# Adafruit_Crickit_for_Circuit_Playground.net
KiCad netlist of a schematic drawn in EAGLE
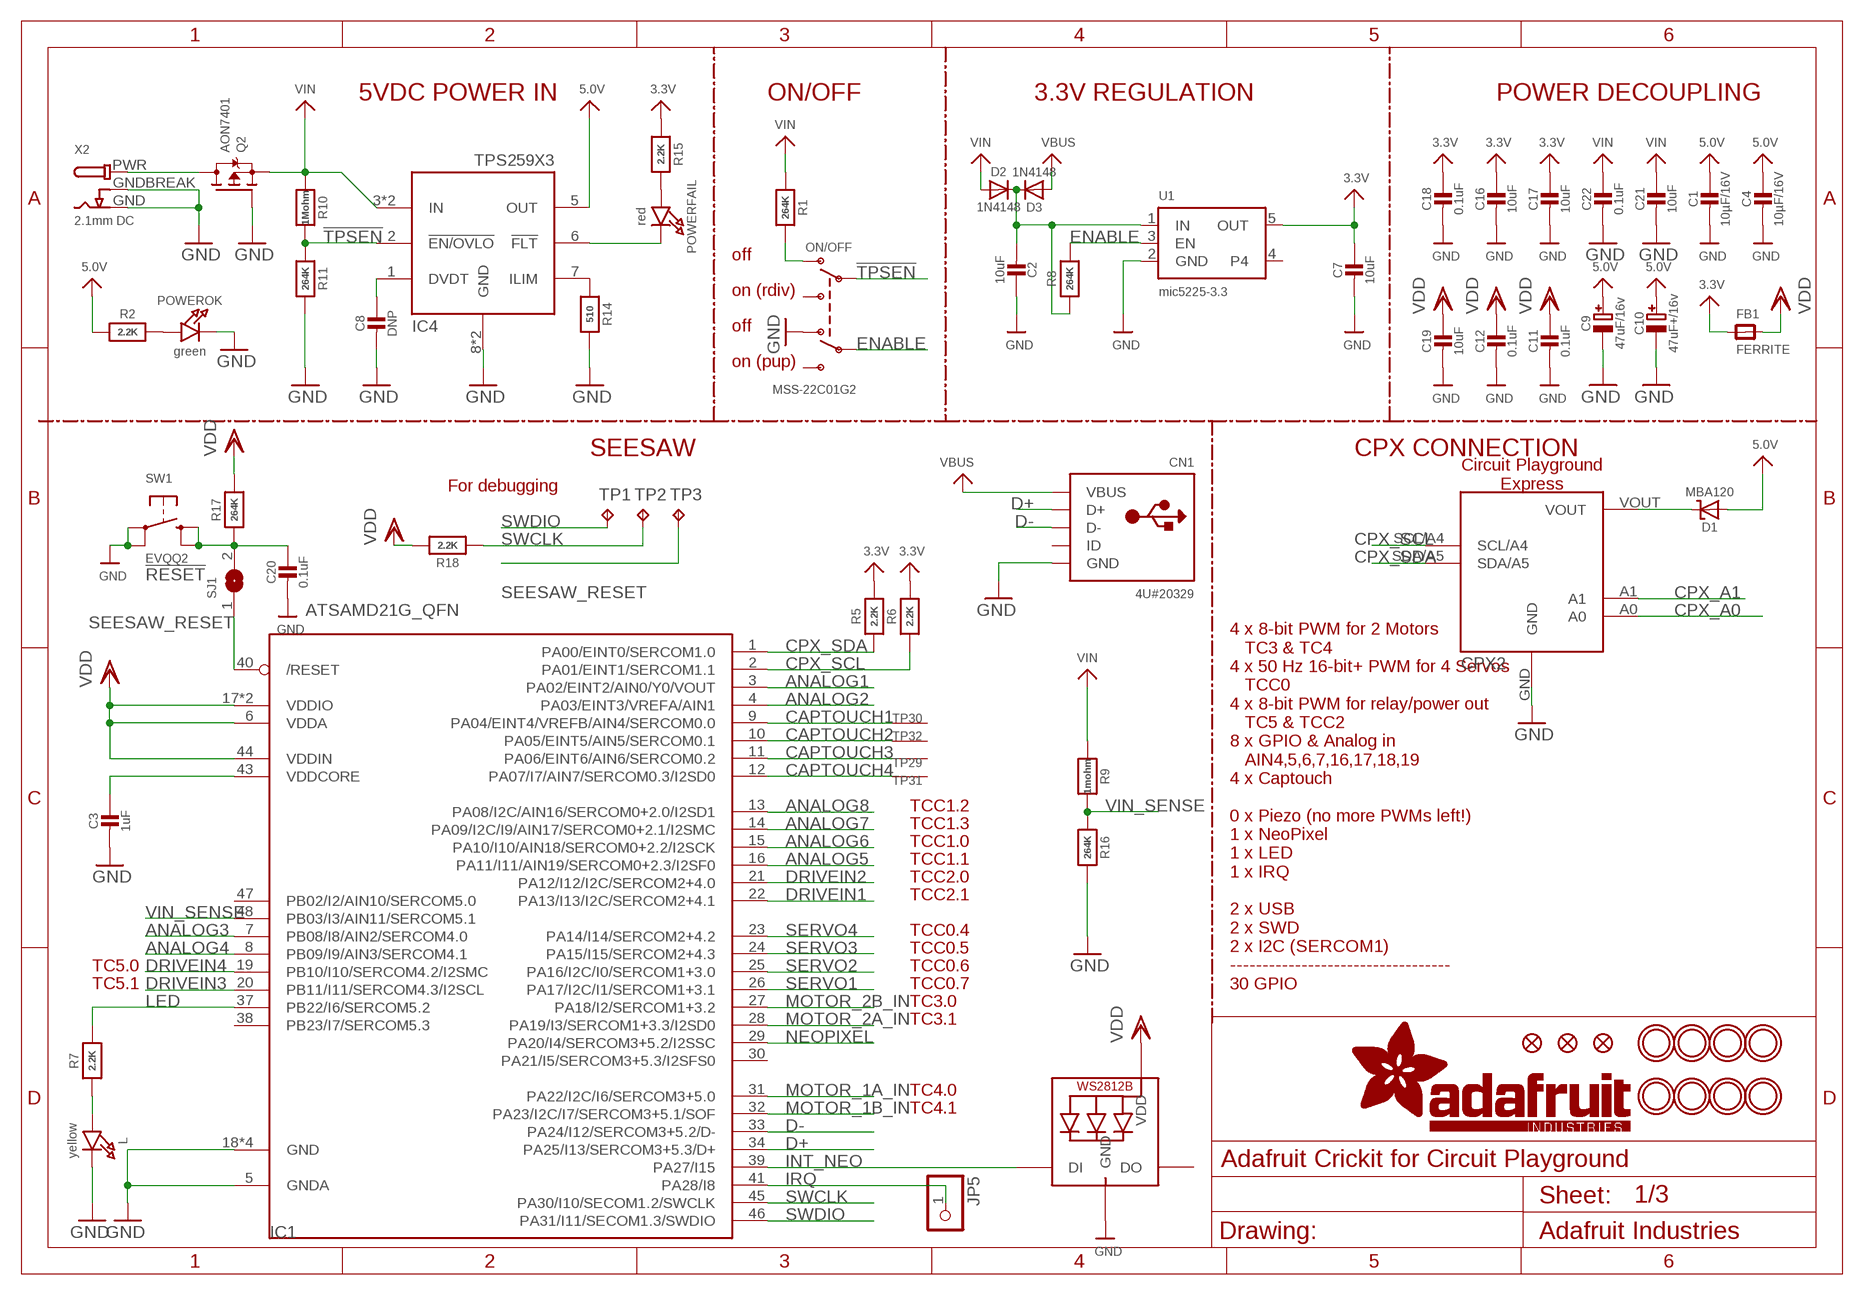
[diagram p0: schematic, sheet 1]
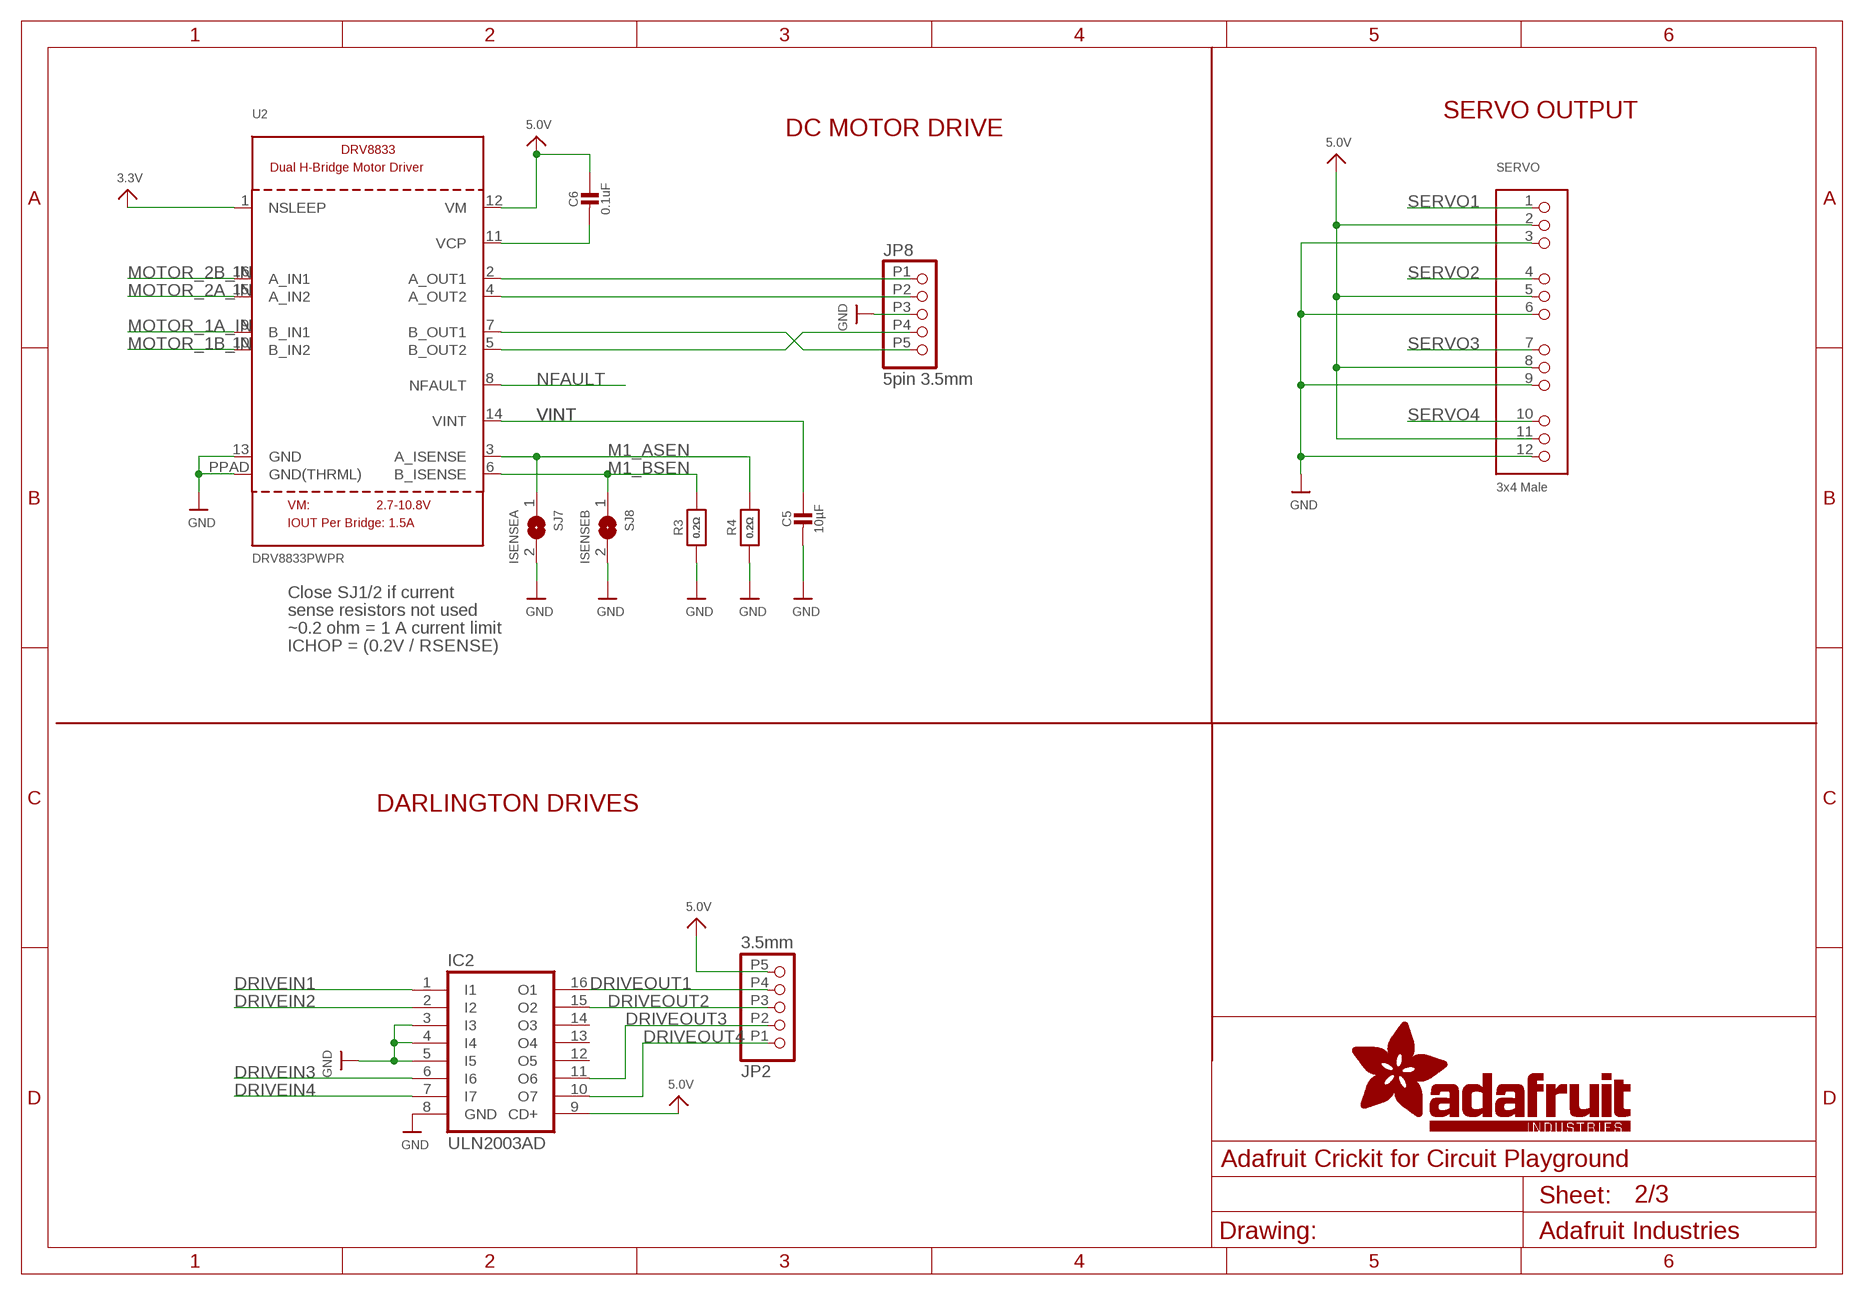
[diagram p1: schematic, sheet 2]
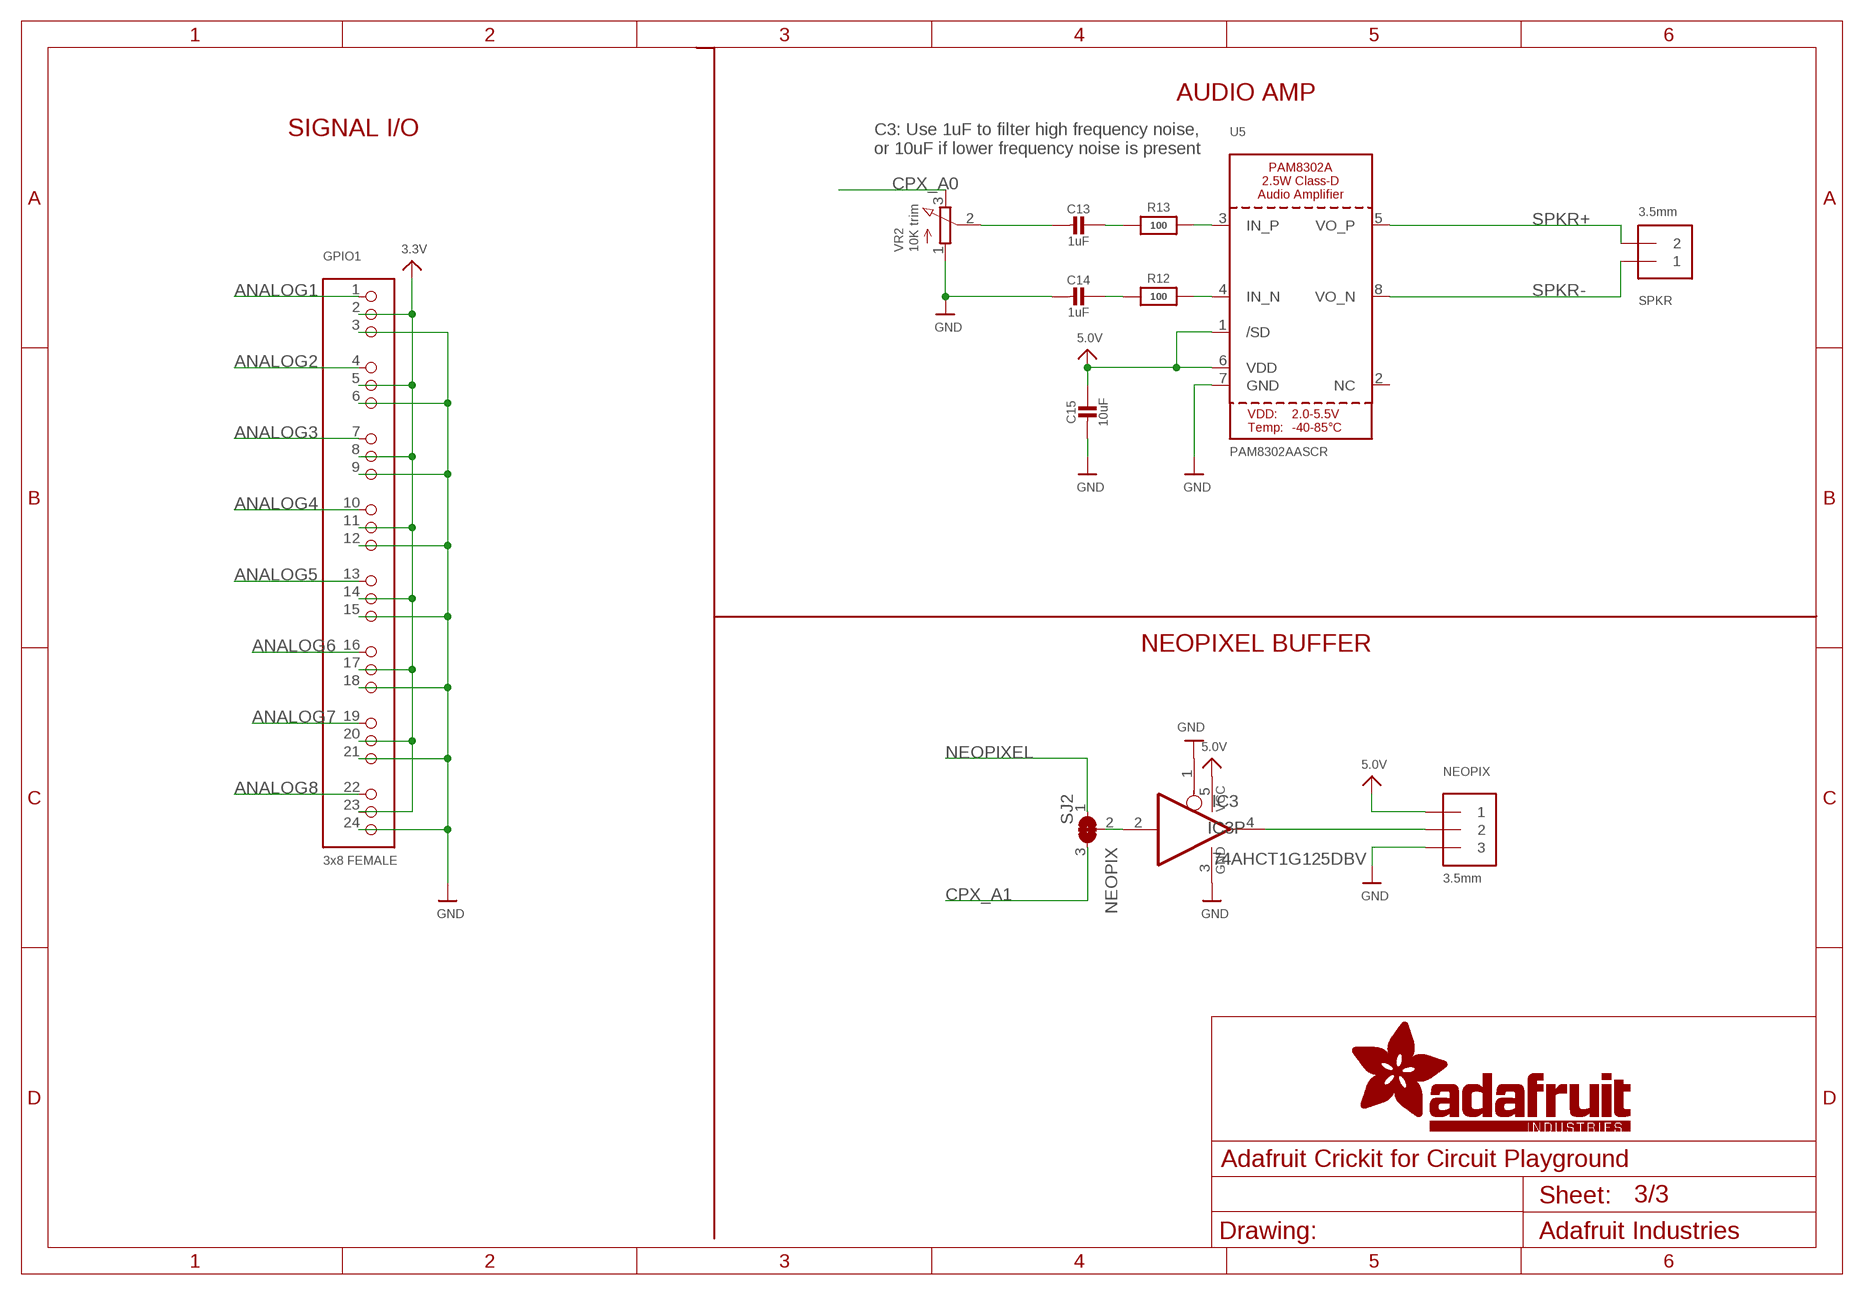
[diagram p2: schematic, sheet 3]

(export (version "E")
  (design (tool "Eeschema 10.0.6"))
  (components
    (comp (ref "C1")
      (value "10µF/16V")
      (footprint "eagle-import:0805-NO")
      (libsource (lib "eagle-import") (part "CAP_CERAMIC0805-NOOUTLINE"))
    )
    (comp (ref "C2")
      (value "10uF")
      (footprint "eagle-import:0805-NO")
      (libsource (lib "eagle-import") (part "CAP_CERAMIC0805-NOOUTLINE"))
    )
    (comp (ref "C3")
      (value "1uF")
      (footprint "eagle-import:0805_10MGAP")
      (libsource (lib "eagle-import") (part "CAP_CERAMIC0805_10MGAP"))
    )
    (comp (ref "C4")
      (value "10µF/16V")
      (footprint "eagle-import:0805-NO")
      (libsource (lib "eagle-import") (part "CAP_CERAMIC0805-NOOUTLINE"))
    )
    (comp (ref "C7")
      (value "10uF")
      (footprint "eagle-import:0805-NO")
      (libsource (lib "eagle-import") (part "CAP_CERAMIC0805-NOOUTLINE"))
    )
    (comp (ref "C8")
      (value "DNP")
      (footprint "eagle-import:0603-NO")
      (libsource (lib "eagle-import") (part "CAP_CERAMIC0603_NO"))
    )
    (comp (ref "C9")
      (value "47uF/16v")
      (footprint "eagle-import:PANASONIC_C")
      (libsource (lib "eagle-import") (part "CAP_ELECTROLYTICPANASONIC_C"))
    )
    (comp (ref "C10")
      (value "47uF+/16v")
      (footprint "eagle-import:PANASONIC_C")
      (libsource (lib "eagle-import") (part "CAP_ELECTROLYTICPANASONIC_C"))
    )
    (comp (ref "C11")
      (value "0.1uF")
      (footprint "eagle-import:0805-NO")
      (libsource (lib "eagle-import") (part "CAP_CERAMIC0805-NOOUTLINE"))
    )
    (comp (ref "C12")
      (value "0.1uF")
      (footprint "eagle-import:0603-NO")
      (libsource (lib "eagle-import") (part "CAP_CERAMIC0603_NO"))
    )
    (comp (ref "C16")
      (value "10uF")
      (footprint "eagle-import:0805-NO")
      (libsource (lib "eagle-import") (part "CAP_CERAMIC0805-NOOUTLINE"))
    )
    (comp (ref "C17")
      (value "10uF")
      (footprint "eagle-import:0805-NO")
      (libsource (lib "eagle-import") (part "CAP_CERAMIC0805-NOOUTLINE"))
    )
    (comp (ref "C18")
      (value "0.1uF")
      (footprint "eagle-import:0805-NO")
      (libsource (lib "eagle-import") (part "CAP_CERAMIC0805-NOOUTLINE"))
    )
    (comp (ref "C19")
      (value "10uF")
      (footprint "eagle-import:0805-NO")
      (libsource (lib "eagle-import") (part "CAP_CERAMIC0805-NOOUTLINE"))
    )
    (comp (ref "C20")
      (value "0.1uF")
      (footprint "eagle-import:0805-NO")
      (libsource (lib "eagle-import") (part "CAP_CERAMIC0805-NOOUTLINE"))
    )
    (comp (ref "C21")
      (value "10uF")
      (footprint "eagle-import:0805-NO")
      (libsource (lib "eagle-import") (part "CAP_CERAMIC0805-NOOUTLINE"))
    )
    (comp (ref "C22")
      (value "0.1uF")
      (footprint "eagle-import:0805-NO")
      (libsource (lib "eagle-import") (part "CAP_CERAMIC0805-NOOUTLINE"))
    )
    (comp (ref "CN1")
      (value "4U#20329")
      (footprint "eagle-import:4UCONN_20329_V2")
      (libsource (lib "eagle-import") (part "USB_MICRO_20329_V2"))
    )
    (comp (ref "CPX2")
      (value "CPX_CRICKIT")
      (footprint "eagle-import:CPX_CRICKIT")
      (libsource (lib "eagle-import") (part "CPX_CRICKIT"))
    )
    (comp (ref "D1")
      (value "MBA120")
      (footprint "eagle-import:SOD-123")
      (libsource (lib "eagle-import") (part "DIODE-SCHOTTKYSOD-123"))
    )
    (comp (ref "D2")
      (value "1N4148")
      (footprint "eagle-import:SOD-323")
      (libsource (lib "eagle-import") (part "DIODESOD-323"))
    )
    (comp (ref "D3")
      (value "1N4148")
      (footprint "eagle-import:SOD-323")
      (libsource (lib "eagle-import") (part "DIODESOD-323"))
    )
    (comp (ref "FB1")
      (value "FERRITE")
      (footprint "eagle-import:0805-NO")
      (libsource (lib "eagle-import") (part "FERRITE-0805NO"))
    )
    (comp (ref "FID1")
      (value "FIDUCIAL_1MM")
      (footprint "eagle-import:FIDUCIAL_1MM")
      (libsource (lib "eagle-import") (part "FIDUCIAL_1MM"))
    )
    (comp (ref "FID2")
      (value "FIDUCIAL_1MM")
      (footprint "eagle-import:FIDUCIAL_1MM")
      (libsource (lib "eagle-import") (part "FIDUCIAL_1MM"))
    )
    (comp (ref "FID3")
      (value "FIDUCIAL_1MM")
      (footprint "eagle-import:FIDUCIAL_1MM")
      (libsource (lib "eagle-import") (part "FIDUCIAL_1MM"))
    )
    (comp (ref "IC1")
      (value "ATSAMD21G_QFN")
      (footprint "eagle-import:TQFN48_7MM")
      (libsource (lib "eagle-import") (part "ATSAMD21G_QFN"))
    )
    (comp (ref "IC4")
      (value "TPS259573")
      (footprint "eagle-import:WSON8")
      (libsource (lib "eagle-import") (part "TPS2595X3"))
    )
    (comp (ref "JP5")
      (value "HEADER-1X1ROUND")
      (footprint "eagle-import:1X01_ROUND")
      (libsource (lib "eagle-import") (part "HEADER-1X1ROUND"))
    )
    (comp (ref "L")
      (value "yellow")
      (footprint "eagle-import:CHIPLED_0805_NOOUTLINE")
      (libsource (lib "eagle-import") (part "LED0805_NOOUTLINE"))
    )
    (comp (ref "LED1")
      (value "WS2812B3535")
      (footprint "eagle-import:LED3535")
      (libsource (lib "eagle-import") (part "WS2812B3535"))
    )
    (comp (ref "ON/OFF")
      (value "MSS-22C01G2")
      (footprint "eagle-import:EG1390")
      (libsource (lib "eagle-import") (part "SWITCH_DPDTEG1390"))
    )
    (comp (ref "POWERFAIL")
      (value "red")
      (footprint "eagle-import:CHIPLED_0805_NOOUTLINE")
      (libsource (lib "eagle-import") (part "LED0805_NOOUTLINE"))
    )
    (comp (ref "POWEROK")
      (value "green")
      (footprint "eagle-import:CHIPLED_0805_NOOUTLINE")
      (libsource (lib "eagle-import") (part "LED0805_NOOUTLINE"))
    )
    (comp (ref "Q2")
      (value "AON7401")
      (footprint "eagle-import:POWERDI3333")
      (libsource (lib "eagle-import") (part "MOSFET-P-POWERDI3333"))
    )
    (comp (ref "R1")
      (value "264K")
      (footprint "eagle-import:0603-NO")
      (libsource (lib "eagle-import") (part "RESISTOR_0603_NOOUT"))
    )
    (comp (ref "R2")
      (value "2.2K")
      (footprint "eagle-import:0603-NO")
      (libsource (lib "eagle-import") (part "RESISTOR_0603_NOOUT"))
    )
    (comp (ref "R5")
      (value "2.2K")
      (footprint "eagle-import:0603-NO")
      (libsource (lib "eagle-import") (part "RESISTOR_0603_NOOUT"))
    )
    (comp (ref "R6")
      (value "2.2K")
      (footprint "eagle-import:0603-NO")
      (libsource (lib "eagle-import") (part "RESISTOR_0603_NOOUT"))
    )
    (comp (ref "R7")
      (value "2.2K")
      (footprint "eagle-import:0603-NO")
      (libsource (lib "eagle-import") (part "RESISTOR_0603_NOOUT"))
    )
    (comp (ref "R8")
      (value "264K")
      (footprint "eagle-import:0603-NO")
      (libsource (lib "eagle-import") (part "RESISTOR_0603_NOOUT"))
    )
    (comp (ref "R9")
      (value "1mohm")
      (footprint "eagle-import:0603-NO")
      (libsource (lib "eagle-import") (part "RESISTOR_0603_NOOUT"))
    )
    (comp (ref "R10")
      (value "1Mohm")
      (footprint "eagle-import:0603-NO")
      (libsource (lib "eagle-import") (part "RESISTOR_0603_NOOUT"))
    )
    (comp (ref "R11")
      (value "264K")
      (footprint "eagle-import:0603-NO")
      (libsource (lib "eagle-import") (part "RESISTOR_0603_NOOUT"))
    )
    (comp (ref "R14")
      (value "510")
      (footprint "eagle-import:0603-NO")
      (libsource (lib "eagle-import") (part "RESISTOR_0603_NOOUT"))
    )
    (comp (ref "R15")
      (value "2.2K")
      (footprint "eagle-import:0603-NO")
      (libsource (lib "eagle-import") (part "RESISTOR_0603_NOOUT"))
    )
    (comp (ref "R16")
      (value "264K")
      (footprint "eagle-import:0603-NO")
      (libsource (lib "eagle-import") (part "RESISTOR_0603_NOOUT"))
    )
    (comp (ref "R17")
      (value "264K")
      (footprint "eagle-import:0603-NO")
      (libsource (lib "eagle-import") (part "RESISTOR_0603_NOOUT"))
    )
    (comp (ref "R18")
      (value "2.2K")
      (footprint "eagle-import:0603-NO")
      (libsource (lib "eagle-import") (part "RESISTOR_0603_NOOUT"))
    )
    (comp (ref "SJ1")
      (value "SOLDERJUMPERCLOSED")
      (footprint "eagle-import:SOLDERJUMPER_CLOSEDWIRE")
      (libsource (lib "eagle-import") (part "SOLDERJUMPERCLOSED"))
    )
    (comp (ref "SW1")
      (value "EVQQ2")
      (footprint "eagle-import:EVQ-Q2_SMALLER")
      (libsource (lib "eagle-import") (part "SWITCH_TACT_SMT_EVQQ2_SMALL"))
    )
    (comp (ref "TP1")
      (value "TPTP15R")
      (footprint "eagle-import:TP15R")
      (libsource (lib "eagle-import") (part "TPTP15R"))
    )
    (comp (ref "TP2")
      (value "TPTP15R")
      (footprint "eagle-import:TP15R")
      (libsource (lib "eagle-import") (part "TPTP15R"))
    )
    (comp (ref "TP3")
      (value "TPTP15R")
      (footprint "eagle-import:TP15R")
      (libsource (lib "eagle-import") (part "TPTP15R"))
    )
    (comp (ref "TP29")
      (value "SEWTAPPCB_ALLIGATOR")
      (footprint "eagle-import:PCB_ALLI")
      (libsource (lib "eagle-import") (part "SEWTAPPCB_ALLIGATOR"))
    )
    (comp (ref "TP30")
      (value "SEWTAPPCB_ALLIGATOR")
      (footprint "eagle-import:PCB_ALLI")
      (libsource (lib "eagle-import") (part "SEWTAPPCB_ALLIGATOR"))
    )
    (comp (ref "TP31")
      (value "SEWTAPPCB_ALLIGATOR")
      (footprint "eagle-import:PCB_ALLI")
      (libsource (lib "eagle-import") (part "SEWTAPPCB_ALLIGATOR"))
    )
    (comp (ref "TP32")
      (value "SEWTAPPCB_ALLIGATOR")
      (footprint "eagle-import:PCB_ALLI")
      (libsource (lib "eagle-import") (part "SEWTAPPCB_ALLIGATOR"))
    )
    (comp (ref "U$41")
      (value "MOUNTINGHOLE3.0THIN")
      (footprint "eagle-import:MOUNTINGHOLE_3.0_PLATEDTHIN")
      (libsource (lib "eagle-import") (part "MOUNTINGHOLE3.0THIN"))
    )
    (comp (ref "U$42")
      (value "MOUNTINGHOLE3.0THIN")
      (footprint "eagle-import:MOUNTINGHOLE_3.0_PLATEDTHIN")
      (libsource (lib "eagle-import") (part "MOUNTINGHOLE3.0THIN"))
    )
    (comp (ref "U$43")
      (value "MOUNTINGHOLE3.0THIN")
      (footprint "eagle-import:MOUNTINGHOLE_3.0_PLATEDTHIN")
      (libsource (lib "eagle-import") (part "MOUNTINGHOLE3.0THIN"))
    )
    (comp (ref "U$44")
      (value "MOUNTINGHOLE3.0THIN")
      (footprint "eagle-import:MOUNTINGHOLE_3.0_PLATEDTHIN")
      (libsource (lib "eagle-import") (part "MOUNTINGHOLE3.0THIN"))
    )
    (comp (ref "U$49")
      (value "MOUNTINGHOLE3.0THIN")
      (footprint "eagle-import:MOUNTINGHOLE_3.0_PLATEDTHIN")
      (libsource (lib "eagle-import") (part "MOUNTINGHOLE3.0THIN"))
    )
    (comp (ref "U$50")
      (value "MOUNTINGHOLE3.0THIN")
      (footprint "eagle-import:MOUNTINGHOLE_3.0_PLATEDTHIN")
      (libsource (lib "eagle-import") (part "MOUNTINGHOLE3.0THIN"))
    )
    (comp (ref "U$51")
      (value "MOUNTINGHOLE3.0THIN")
      (footprint "eagle-import:MOUNTINGHOLE_3.0_PLATEDTHIN")
      (libsource (lib "eagle-import") (part "MOUNTINGHOLE3.0THIN"))
    )
    (comp (ref "U$52")
      (value "MOUNTINGHOLE3.0THIN")
      (footprint "eagle-import:MOUNTINGHOLE_3.0_PLATEDTHIN")
      (libsource (lib "eagle-import") (part "MOUNTINGHOLE3.0THIN"))
    )
    (comp (ref "U1")
      (value "mic5225-3.3")
      (footprint "eagle-import:SOT23-5")
      (libsource (lib "eagle-import") (part "VREG_SOT23-5"))
    )
    (comp (ref "X2")
      (value "2.1mm DC")
      (footprint "eagle-import:DCJACK_2MM_PTH")
      (libsource (lib "eagle-import") (part "DCBARRELPTH"))
    )
    (comp (ref "C13")
      (value "1uF")
      (footprint "eagle-import:0805-NO")
      (libsource (lib "eagle-import") (part "CAP_CERAMIC0805-NOOUTLINE"))
    )
    (comp (ref "C14")
      (value "1uF")
      (footprint "eagle-import:0805-NO")
      (libsource (lib "eagle-import") (part "CAP_CERAMIC0805-NOOUTLINE"))
    )
    (comp (ref "C15")
      (value "10uF")
      (footprint "eagle-import:0805-NO")
      (libsource (lib "eagle-import") (part "CAP_CERAMIC0805-NOOUTLINE"))
    )
    (comp (ref "GPIO1")
      (value "3x8 FEMALE")
      (footprint "eagle-import:3X08")
      (libsource (lib "eagle-import") (part "HEADER-3X08"))
    )
    (comp (ref "IC3")
      (value "74AHCT1G125DBV")
      (footprint "eagle-import:SOT23-5")
      (libsource (lib "eagle-import") (part "741G125DBVAHCT"))
    )
    (comp (ref "NEOPIX")
      (value "3.5mm")
      (footprint "eagle-import:TERMBLOCK_1X3-3.5MM")
      (libsource (lib "eagle-import") (part "TERMBLOCK_1X3"))
    )
    (comp (ref "R12")
      (value "100")
      (footprint "eagle-import:0603-NO")
      (libsource (lib "eagle-import") (part "RESISTOR_0603_NOOUT"))
    )
    (comp (ref "R13")
      (value "100")
      (footprint "eagle-import:0603-NO")
      (libsource (lib "eagle-import") (part "RESISTOR_0603_NOOUT"))
    )
    (comp (ref "SJ2")
      (value "SOLDERJUMPER_2WAY")
      (footprint "eagle-import:SOLDERJUMPER_2WAY_OPEN_NOPASTE")
      (libsource (lib "eagle-import") (part "SOLDERJUMPER_2WAY"))
    )
    (comp (ref "SPKR")
      (value "3.5mm")
      (footprint "eagle-import:TERMBLOCK_1X2-3.5MM")
      (libsource (lib "eagle-import") (part "TERMBLOCK_1X2"))
    )
    (comp (ref "U5")
      (value "PAM8302AASCR")
      (footprint "eagle-import:MSOP8_0.65MM")
      (libsource (lib "eagle-import") (part "AUDIOAMP_PAM8302A"))
    )
    (comp (ref "VR2")
      (value "10K trim")
      (footprint "eagle-import:TRIMPOT_BOURNS_3303W")
      (libsource (lib "eagle-import") (part "TRIMPOT3303W/X"))
    )
    (comp (ref "C5")
      (value "10µF")
      (footprint "eagle-import:0805-NO")
      (libsource (lib "eagle-import") (part "CAP_CERAMIC0805-NOOUTLINE"))
    )
    (comp (ref "C6")
      (value "0.1uF")
      (footprint "eagle-import:0805-NO")
      (libsource (lib "eagle-import") (part "CAP_CERAMIC0805-NOOUTLINE"))
    )
    (comp (ref "IC2")
      (value "ULN2003AD")
      (footprint "eagle-import:SO16")
      (libsource (lib "eagle-import") (part "ULN2003AD"))
    )
    (comp (ref "JP2")
      (value "3.5mm")
      (footprint "eagle-import:TERMBLOCK_1X5-3.5MM")
      (libsource (lib "eagle-import") (part "HEADER-1X5_3.5TERMINAL"))
    )
    (comp (ref "JP8")
      (value "5pin 3.5mm")
      (footprint "eagle-import:TERMBLOCK_1X5-3.5MM")
      (libsource (lib "eagle-import") (part "HEADER-1X5_3.5TERMINAL"))
    )
    (comp (ref "R3")
      (value "0.2Ω")
      (footprint "eagle-import:_1206")
      (libsource (lib "eagle-import") (part "RESISTOR_1206"))
    )
    (comp (ref "R4")
      (value "0.2Ω")
      (footprint "eagle-import:_1206")
      (libsource (lib "eagle-import") (part "RESISTOR_1206"))
    )
    (comp (ref "SERVO")
      (value "3x4 Male")
      (footprint "eagle-import:3X04")
      (libsource (lib "eagle-import") (part "HEADER-3X04"))
    )
    (comp (ref "SJ7")
      (value "ISENSEA")
      (footprint "eagle-import:SOLDERJUMPER_ARROW_NOPASTE")
      (libsource (lib "eagle-import") (part "SOLDERJUMPER"))
    )
    (comp (ref "SJ8")
      (value "ISENSEB")
      (footprint "eagle-import:SOLDERJUMPER_ARROW_NOPASTE")
      (libsource (lib "eagle-import") (part "SOLDERJUMPER"))
    )
    (comp (ref "U2")
      (value "DRV8833PWPR")
      (footprint "eagle-import:HTSSOP16")
      (libsource (lib "eagle-import") (part "DRV8833"))
    )
  )
  (nets
    (net (code "1") (name "3.3V") (class "Default")
      (node (ref "C16") (pin "1") (pinfunction "1_1") (pintype "passive"))
      (node (ref "C17") (pin "1") (pinfunction "1_1") (pintype "passive"))
      (node (ref "C18") (pin "1") (pinfunction "1_1") (pintype "passive"))
      (node (ref "C7") (pin "1") (pinfunction "1_1") (pintype "passive"))
      (node (ref "FB1") (pin "1") (pinfunction "P$1_1") (pintype "passive"))
      (node (ref "GPIO1") (pin "11") (pinfunction "11_11") (pintype "passive"))
      (node (ref "GPIO1") (pin "14") (pinfunction "14_14") (pintype "passive"))
      (node (ref "GPIO1") (pin "17") (pinfunction "17_17") (pintype "passive"))
      (node (ref "GPIO1") (pin "2") (pinfunction "2_2") (pintype "passive"))
      (node (ref "GPIO1") (pin "20") (pinfunction "20_20") (pintype "passive"))
      (node (ref "GPIO1") (pin "23") (pinfunction "23_23") (pintype "passive"))
      (node (ref "GPIO1") (pin "5") (pinfunction "5_5") (pintype "passive"))
      (node (ref "GPIO1") (pin "8") (pinfunction "8_8") (pintype "passive"))
      (node (ref "R15") (pin "1") (pinfunction "1_1") (pintype "passive"))
      (node (ref "R5") (pin "2") (pinfunction "2_2") (pintype "passive"))
      (node (ref "R6") (pin "2") (pinfunction "2_2") (pintype "passive"))
      (node (ref "U1") (pin "5") (pinfunction "OUT_5") (pintype "power_in"))
      (node (ref "U2") (pin "1") (pinfunction "NSLEEP_1") (pintype "input"))
    )
    (net (code "2") (name "5.0V") (class "Default")
      (node (ref "C1") (pin "1") (pinfunction "1_1") (pintype "passive"))
      (node (ref "C10") (pin "+") (pinfunction "+_+") (pintype "passive"))
      (node (ref "C15") (pin "1") (pinfunction "1_1") (pintype "passive"))
      (node (ref "C4") (pin "1") (pinfunction "1_1") (pintype "passive"))
      (node (ref "C6") (pin "1") (pinfunction "1_1") (pintype "passive"))
      (node (ref "C9") (pin "+") (pinfunction "+_+") (pintype "passive"))
      (node (ref "D1") (pin "A") (pinfunction "A_A") (pintype "passive"))
      (node (ref "IC2") (pin "9") (pinfunction "CD+_9") (pintype "passive"))
      (node (ref "IC3") (pin "5") (pinfunction "VCC_5") (pintype "power_in"))
      (node (ref "IC4") (pin "5") (pinfunction "OUT_5") (pintype "power_in"))
      (node (ref "JP2") (pin "P5") (pinfunction "5_P5") (pintype "passive"))
      (node (ref "NEOPIX") (pin "1") (pinfunction "1_1") (pintype "passive"))
      (node (ref "R2") (pin "1") (pinfunction "1_1") (pintype "passive"))
      (node (ref "SERVO") (pin "11") (pinfunction "11_11") (pintype "passive"))
      (node (ref "SERVO") (pin "2") (pinfunction "2_2") (pintype "passive"))
      (node (ref "SERVO") (pin "5") (pinfunction "5_5") (pintype "passive"))
      (node (ref "SERVO") (pin "8") (pinfunction "8_8") (pintype "passive"))
      (node (ref "U2") (pin "12") (pinfunction "VM_12") (pintype "power_in"))
      (node (ref "U5") (pin "1") (pinfunction "/SD_1") (pintype "input"))
      (node (ref "U5") (pin "6") (pinfunction "VDD_6") (pintype "power_in"))
    )
    (net (code "3") (name "ANALOG1") (class "Default")
      (node (ref "GPIO1") (pin "1") (pinfunction "1_1") (pintype "passive"))
      (node (ref "IC1") (pin "3") (pinfunction "PA02/EINT2/AIN0/Y0/VOUT_3") (pintype "bidirectional"))
    )
    (net (code "4") (name "ANALOG2") (class "Default")
      (node (ref "GPIO1") (pin "4") (pinfunction "4_4") (pintype "passive"))
      (node (ref "IC1") (pin "4") (pinfunction "PA03/EINT3/VREFA/AIN1_4") (pintype "bidirectional"))
    )
    (net (code "5") (name "ANALOG3") (class "Default")
      (node (ref "GPIO1") (pin "7") (pinfunction "7_7") (pintype "passive"))
      (node (ref "IC1") (pin "7") (pinfunction "PB08/I8/AIN2/SERCOM4.0_7") (pintype "bidirectional"))
    )
    (net (code "6") (name "ANALOG4") (class "Default")
      (node (ref "GPIO1") (pin "10") (pinfunction "10_10") (pintype "passive"))
      (node (ref "IC1") (pin "8") (pinfunction "PB09/I9/AIN3/SERCOM4.1_8") (pintype "bidirectional"))
    )
    (net (code "7") (name "ANALOG5") (class "Default")
      (node (ref "GPIO1") (pin "13") (pinfunction "13_13") (pintype "passive"))
      (node (ref "IC1") (pin "16") (pinfunction "PA11/I11/AIN19/SERCOM0+2.3/I2SF0_16") (pintype "bidirectional"))
    )
    (net (code "8") (name "ANALOG6") (class "Default")
      (node (ref "GPIO1") (pin "16") (pinfunction "16_16") (pintype "passive"))
      (node (ref "IC1") (pin "15") (pinfunction "PA10/I10/AIN18/SERCOM0+2.2/I2SCK_15") (pintype "bidirectional"))
    )
    (net (code "9") (name "ANALOG7") (class "Default")
      (node (ref "GPIO1") (pin "19") (pinfunction "19_19") (pintype "passive"))
      (node (ref "IC1") (pin "14") (pinfunction "PA09/I2C/I9/AIN17/SERCOM0+2.1/I2SMC_14") (pintype "bidirectional"))
    )
    (net (code "10") (name "ANALOG8") (class "Default")
      (node (ref "GPIO1") (pin "22") (pinfunction "22_22") (pintype "passive"))
      (node (ref "IC1") (pin "13") (pinfunction "PA08/I2C/AIN16/SERCOM0+2.0/I2SD1_13") (pintype "bidirectional"))
    )
    (net (code "11") (name "CAPTOUCH1") (class "Default")
      (node (ref "IC1") (pin "9") (pinfunction "PA04/EINT4/VREFB/AIN4/SERCOM0.0_9") (pintype "bidirectional"))
      (node (ref "TP30") (pin "P$1") (pinfunction "SEW_P$1") (pintype "bidirectional"))
    )
    (net (code "12") (name "CAPTOUCH2") (class "Default")
      (node (ref "IC1") (pin "10") (pinfunction "PA05/EINT5/AIN5/SERCOM0.1_10") (pintype "bidirectional"))
      (node (ref "TP32") (pin "P$1") (pinfunction "SEW_P$1") (pintype "bidirectional"))
    )
    (net (code "13") (name "CAPTOUCH3") (class "Default")
      (node (ref "IC1") (pin "11") (pinfunction "PA06/EINT6/AIN6/SERCOM0.2_11") (pintype "bidirectional"))
      (node (ref "TP29") (pin "P$1") (pinfunction "SEW_P$1") (pintype "bidirectional"))
    )
    (net (code "14") (name "CAPTOUCH4") (class "Default")
      (node (ref "IC1") (pin "12") (pinfunction "PA07/I7/AIN7/SERCOM0.3/I2SD0_12") (pintype "bidirectional"))
      (node (ref "TP31") (pin "P$1") (pinfunction "SEW_P$1") (pintype "bidirectional"))
    )
    (net (code "15") (name "CPX_A0") (class "Default")
      (node (ref "CPX2") (pin "A0") (pinfunction "A0_A0") (pintype "bidirectional"))
      (node (ref "VR2") (pin "3") (pinfunction "E_3") (pintype "passive"))
    )
    (net (code "16") (name "CPX_A1") (class "Default")
      (node (ref "CPX2") (pin "A1") (pinfunction "A1_A1") (pintype "bidirectional"))
      (node (ref "SJ2") (pin "3") (pinfunction "3_3") (pintype "passive"))
    )
    (net (code "17") (name "CPX_SCL") (class "Default")
      (node (ref "CPX2") (pin "SCL/A4") (pinfunction "SCL/A4_SCL/A4") (pintype "bidirectional"))
      (node (ref "IC1") (pin "2") (pinfunction "PA01/EINT1/SERCOM1.1_2") (pintype "bidirectional"))
      (node (ref "R6") (pin "1") (pinfunction "1_1") (pintype "passive"))
    )
    (net (code "18") (name "CPX_SDA") (class "Default")
      (node (ref "CPX2") (pin "SDA/A5") (pinfunction "SDA/A5_SDA/A5") (pintype "bidirectional"))
      (node (ref "IC1") (pin "1") (pinfunction "PA00/EINT0/SERCOM1.0_1") (pintype "bidirectional"))
      (node (ref "R5") (pin "1") (pinfunction "1_1") (pintype "passive"))
    )
    (net (code "19") (name "D+") (class "Default")
      (node (ref "CN1") (pin "D+") (pinfunction "D+_D+") (pintype "bidirectional"))
      (node (ref "IC1") (pin "34") (pinfunction "PA25/I13/SERCOM3+5.3/D+_34") (pintype "bidirectional"))
    )
    (net (code "20") (name "D-") (class "Default")
      (node (ref "CN1") (pin "D-") (pinfunction "D-_D-") (pintype "bidirectional"))
      (node (ref "IC1") (pin "33") (pinfunction "PA24/I12/SERCOM3+5.2/D-_33") (pintype "bidirectional"))
    )
    (net (code "21") (name "DRIVEIN1") (class "Default")
      (node (ref "IC1") (pin "22") (pinfunction "PA13/I13/I2C/SERCOM2+4.1_22") (pintype "bidirectional"))
      (node (ref "IC2") (pin "1") (pinfunction "I1_1") (pintype "input"))
    )
    (net (code "22") (name "DRIVEIN2") (class "Default")
      (node (ref "IC1") (pin "21") (pinfunction "PA12/I12/I2C/SERCOM2+4.0_21") (pintype "bidirectional"))
      (node (ref "IC2") (pin "2") (pinfunction "I2_2") (pintype "input"))
    )
    (net (code "23") (name "DRIVEIN3") (class "Default")
      (node (ref "IC1") (pin "20") (pinfunction "PB11/I11/SERCOM4.3/I2SCL_20") (pintype "bidirectional"))
      (node (ref "IC2") (pin "6") (pinfunction "I6_6") (pintype "input"))
    )
    (net (code "24") (name "DRIVEIN4") (class "Default")
      (node (ref "IC1") (pin "19") (pinfunction "PB10/I10/SERCOM4.2/I2SMC_19") (pintype "bidirectional"))
      (node (ref "IC2") (pin "7") (pinfunction "I7_7") (pintype "input"))
    )
    (net (code "25") (name "DRIVEOUT1") (class "Default")
      (node (ref "IC2") (pin "16") (pinfunction "O1_16") (pintype "open_collector"))
      (node (ref "JP2") (pin "P4") (pinfunction "4_P4") (pintype "passive"))
    )
    (net (code "26") (name "DRIVEOUT2") (class "Default")
      (node (ref "IC2") (pin "15") (pinfunction "O2_15") (pintype "open_collector"))
      (node (ref "JP2") (pin "P3") (pinfunction "3_P3") (pintype "passive"))
    )
    (net (code "27") (name "DRIVEOUT3") (class "Default")
      (node (ref "IC2") (pin "11") (pinfunction "O6_11") (pintype "open_collector"))
      (node (ref "JP2") (pin "P2") (pinfunction "2_P2") (pintype "passive"))
    )
    (net (code "28") (name "DRIVEOUT4") (class "Default")
      (node (ref "IC2") (pin "10") (pinfunction "O7_10") (pintype "open_collector"))
      (node (ref "JP2") (pin "P1") (pinfunction "1_P1") (pintype "passive"))
    )
    (net (code "29") (name "ENABLE") (class "Default")
      (node (ref "ON/OFF") (pin "P2") (pinfunction "P2_P2") (pintype "passive"))
      (node (ref "R8") (pin "2") (pinfunction "2_2") (pintype "passive"))
      (node (ref "U1") (pin "3") (pinfunction "EN_3") (pintype "input"))
    )
    (net (code "30") (name "GND") (class "Default")
      (node (ref "C1") (pin "2") (pinfunction "2_2") (pintype "passive"))
      (node (ref "C10") (pin "-") (pinfunction "-_-") (pintype "passive"))
      (node (ref "C11") (pin "2") (pinfunction "2_2") (pintype "passive"))
      (node (ref "C12") (pin "2") (pinfunction "2_2") (pintype "passive"))
      (node (ref "C14") (pin "2") (pinfunction "2_2") (pintype "passive"))
      (node (ref "C15") (pin "2") (pinfunction "2_2") (pintype "passive"))
      (node (ref "C16") (pin "2") (pinfunction "2_2") (pintype "passive"))
      (node (ref "C17") (pin "2") (pinfunction "2_2") (pintype "passive"))
      (node (ref "C18") (pin "2") (pinfunction "2_2") (pintype "passive"))
      (node (ref "C19") (pin "2") (pinfunction "2_2") (pintype "passive"))
      (node (ref "C2") (pin "1") (pinfunction "1_1") (pintype "passive"))
      (node (ref "C20") (pin "2") (pinfunction "2_2") (pintype "passive"))
      (node (ref "C21") (pin "2") (pinfunction "2_2") (pintype "passive"))
      (node (ref "C22") (pin "2") (pinfunction "2_2") (pintype "passive"))
      (node (ref "C3") (pin "2") (pinfunction "2_2") (pintype "passive"))
      (node (ref "C4") (pin "2") (pinfunction "2_2") (pintype "passive"))
      (node (ref "C5") (pin "2") (pinfunction "2_2") (pintype "passive"))
      (node (ref "C7") (pin "2") (pinfunction "2_2") (pintype "passive"))
      (node (ref "C8") (pin "2") (pinfunction "2_2") (pintype "passive"))
      (node (ref "C9") (pin "-") (pinfunction "-_-") (pintype "passive"))
      (node (ref "CN1") (pin "BASE@1") (pinfunction "GND_BASE@1") (pintype "power_in"))
      (node (ref "CN1") (pin "BASE@2") (pinfunction "GND_BASE@2") (pintype "power_in"))
      (node (ref "CN1") (pin "GND") (pinfunction "GND_GND") (pintype "power_in"))
      (node (ref "CN1") (pin "SPRT@1") (pinfunction "GND_SPRT@1") (pintype "power_in"))
      (node (ref "CN1") (pin "SPRT@2") (pinfunction "GND_SPRT@2") (pintype "power_in"))
      (node (ref "CN1") (pin "SPRT@3") (pinfunction "GND_SPRT@3") (pintype "power_in"))
      (node (ref "CN1") (pin "SPRT@4") (pinfunction "GND_SPRT@4") (pintype "power_in"))
      (node (ref "CPX2") (pin "GND") (pinfunction "GND_GND") (pintype "power_in"))
      (node (ref "GPIO1") (pin "12") (pinfunction "12_12") (pintype "passive"))
      (node (ref "GPIO1") (pin "15") (pinfunction "15_15") (pintype "passive"))
      (node (ref "GPIO1") (pin "18") (pinfunction "18_18") (pintype "passive"))
      (node (ref "GPIO1") (pin "21") (pinfunction "21_21") (pintype "passive"))
      (node (ref "GPIO1") (pin "24") (pinfunction "24_24") (pintype "passive"))
      (node (ref "GPIO1") (pin "3") (pinfunction "3_3") (pintype "passive"))
      (node (ref "GPIO1") (pin "6") (pinfunction "6_6") (pintype "passive"))
      (node (ref "GPIO1") (pin "9") (pinfunction "9_9") (pintype "passive"))
      (node (ref "IC1") (pin "18") (pinfunction "GND_18") (pintype "power_in"))
      (node (ref "IC1") (pin "35") (pinfunction "GND_35") (pintype "power_in"))
      (node (ref "IC1") (pin "42") (pinfunction "GND_42") (pintype "power_in"))
      (node (ref "IC1") (pin "5") (pinfunction "GNDA_5") (pintype "power_in"))
      (node (ref "IC1") (pin "THERMAL") (pinfunction "GND_THERMAL") (pintype "power_in"))
      (node (ref "IC2") (pin "3") (pinfunction "I3_3") (pintype "input"))
      (node (ref "IC2") (pin "4") (pinfunction "I4_4") (pintype "input"))
      (node (ref "IC2") (pin "5") (pinfunction "I5_5") (pintype "input"))
      (node (ref "IC2") (pin "8") (pinfunction "GND_8") (pintype "power_in"))
      (node (ref "IC3") (pin "1") (pinfunction "OE_1") (pintype "input"))
      (node (ref "IC3") (pin "3") (pinfunction "GND_3") (pintype "power_in"))
      (node (ref "IC4") (pin "8") (pinfunction "GND_8") (pintype "power_in"))
      (node (ref "IC4") (pin "PAD") (pinfunction "GND_PAD") (pintype "power_in"))
      (node (ref "JP8") (pin "P3") (pinfunction "3_P3") (pintype "passive"))
      (node (ref "L") (pin "C") (pinfunction "C_C") (pintype "passive"))
      (node (ref "LED1") (pin "4") (pinfunction "GND_4") (pintype "power_in"))
      (node (ref "NEOPIX") (pin "3") (pinfunction "3_3") (pintype "passive"))
      (node (ref "ON/OFF") (pin "O2") (pinfunction "O2_O2") (pintype "passive"))
      (node (ref "POWEROK") (pin "C") (pinfunction "C_C") (pintype "passive"))
      (node (ref "Q2") (pin "4") (pinfunction "G_4") (pintype "passive"))
      (node (ref "R11") (pin "2") (pinfunction "2_2") (pintype "passive"))
      (node (ref "R14") (pin "2") (pinfunction "2_2") (pintype "passive"))
      (node (ref "R16") (pin "2") (pinfunction "2_2") (pintype "passive"))
      (node (ref "R3") (pin "1") (pinfunction "1_1") (pintype "passive"))
      (node (ref "R4") (pin "1") (pinfunction "1_1") (pintype "passive"))
      (node (ref "SERVO") (pin "12") (pinfunction "12_12") (pintype "passive"))
      (node (ref "SERVO") (pin "3") (pinfunction "3_3") (pintype "passive"))
      (node (ref "SERVO") (pin "6") (pinfunction "6_6") (pintype "passive"))
      (node (ref "SERVO") (pin "9") (pinfunction "9_9") (pintype "passive"))
      (node (ref "SJ7") (pin "2") (pinfunction "2_2") (pintype "passive"))
      (node (ref "SJ8") (pin "2") (pinfunction "2_2") (pintype "passive"))
      (node (ref "SW1") (pin "A") (pinfunction "P_A") (pintype "passive"))
      (node (ref "SW1") (pin "A'") (pinfunction "P1_A'") (pintype "passive"))
      (node (ref "U1") (pin "2") (pinfunction "GND_2") (pintype "power_in"))
      (node (ref "U2") (pin "13") (pinfunction "GND_13") (pintype "power_in"))
      (node (ref "U2") (pin "PPAD") (pinfunction "GND(THRML)_PPAD") (pintype "power_in"))
      (node (ref "U5") (pin "7") (pinfunction "GND_7") (pintype "power_in"))
      (node (ref "VR2") (pin "1") (pinfunction "A_1") (pintype "passive"))
      (node (ref "X2") (pin "GND") (pinfunction "GND_GND") (pintype "power_in"))
      (node (ref "X2") (pin "GNDBREAK") (pinfunction "GNDBREAK_GNDBREAK") (pintype "power_in"))
    )
    (net (code "31") (name "INT_NEO") (class "Default")
      (node (ref "IC1") (pin "39") (pinfunction "PA27/I15_39") (pintype "bidirectional"))
      (node (ref "LED1") (pin "1") (pinfunction "DI_1") (pintype "input"))
    )
    (net (code "32") (name "IRQ") (class "Default")
      (node (ref "IC1") (pin "41") (pinfunction "PA28/I8_41") (pintype "bidirectional"))
      (node (ref "JP5") (pin "1") (pinfunction "1_1") (pintype "passive"))
    )
    (net (code "33") (name "LED") (class "Default")
      (node (ref "IC1") (pin "37") (pinfunction "PB22/I6/SERCOM5.2_37") (pintype "bidirectional"))
      (node (ref "R7") (pin "2") (pinfunction "2_2") (pintype "passive"))
    )
    (net (code "34") (name "M1_ASEN") (class "Default")
      (node (ref "R4") (pin "2") (pinfunction "2_2") (pintype "passive"))
      (node (ref "SJ7") (pin "1") (pinfunction "1_1") (pintype "passive"))
      (node (ref "U2") (pin "3") (pinfunction "A_ISENSE_3") (pintype "bidirectional"))
    )
    (net (code "35") (name "M1_BSEN") (class "Default")
      (node (ref "R3") (pin "2") (pinfunction "2_2") (pintype "passive"))
      (node (ref "SJ8") (pin "1") (pinfunction "1_1") (pintype "passive"))
      (node (ref "U2") (pin "6") (pinfunction "B_ISENSE_6") (pintype "bidirectional"))
    )
    (net (code "36") (name "MOTOR_1A_IN") (class "Default")
      (node (ref "IC1") (pin "31") (pinfunction "PA22/I2C/I6/SERCOM3+5.0_31") (pintype "bidirectional"))
      (node (ref "U2") (pin "9") (pinfunction "B_IN1_9") (pintype "input"))
    )
    (net (code "37") (name "MOTOR_1B_IN") (class "Default")
      (node (ref "IC1") (pin "32") (pinfunction "PA23/I2C/I7/SERCOM3+5.1/SOF_32") (pintype "bidirectional"))
      (node (ref "U2") (pin "10") (pinfunction "B_IN2_10") (pintype "input"))
    )
    (net (code "38") (name "MOTOR_2A_IN") (class "Default")
      (node (ref "IC1") (pin "28") (pinfunction "PA19/I3/SERCOM1+3.3/I2SD0_28") (pintype "bidirectional"))
      (node (ref "U2") (pin "15") (pinfunction "A_IN2_15") (pintype "input"))
    )
    (net (code "39") (name "MOTOR_2B_IN") (class "Default")
      (node (ref "IC1") (pin "27") (pinfunction "PA18/I2/SERCOM1+3.2_27") (pintype "bidirectional"))
      (node (ref "U2") (pin "16") (pinfunction "A_IN1_16") (pintype "input"))
    )
    (net (code "40") (name "NEOPIX") (class "Default")
      (node (ref "IC3") (pin "2") (pinfunction "I_2") (pintype "input"))
      (node (ref "SJ2") (pin "2") (pinfunction "2_2") (pintype "passive"))
    )
    (net (code "41") (name "NEOPIXEL") (class "Default")
      (node (ref "IC1") (pin "29") (pinfunction "PA20/I4/SERCOM3+5.2/I2SSC_29") (pintype "bidirectional"))
      (node (ref "SJ2") (pin "1") (pinfunction "1_1") (pintype "passive"))
    )
    (net (code "42") (name "NFAULT") (class "Default")
      (node (ref "U2") (pin "8") (pinfunction "NFAULT_8") (pintype "bidirectional"))
    )
    (net (code "43") (name "Net-(C13-Pad1)") (class "Default")
      (node (ref "C13") (pin "1") (pinfunction "1_1") (pintype "passive"))
      (node (ref "R13") (pin "1") (pinfunction "1_1") (pintype "passive"))
    )
    (net (code "44") (name "Net-(C14-Pad1)") (class "Default")
      (node (ref "C14") (pin "1") (pinfunction "1_1") (pintype "passive"))
      (node (ref "R12") (pin "1") (pinfunction "1_1") (pintype "passive"))
    )
    (net (code "45") (name "Net-(CPX2-PadVOUT)") (class "Default")
      (node (ref "CPX2") (pin "VOUT") (pinfunction "VOUT_VOUT") (pintype "power_in"))
      (node (ref "D1") (pin "C") (pinfunction "C_C") (pintype "passive"))
    )
    (net (code "46") (name "Net-(IC1-VDDCORE)") (class "Default")
      (node (ref "C3") (pin "1") (pinfunction "1_1") (pintype "passive"))
      (node (ref "IC1") (pin "43") (pinfunction "VDDCORE_43") (pintype "power_in"))
    )
    (net (code "47") (name "Net-(IC3A-O)") (class "Default")
      (node (ref "IC3") (pin "4") (pinfunction "O_4") (pintype "tri_state"))
      (node (ref "NEOPIX") (pin "2") (pinfunction "2_2") (pintype "passive"))
    )
    (net (code "48") (name "Net-(IC4-DVDT)") (class "Default")
      (node (ref "C8") (pin "1") (pinfunction "1_1") (pintype "passive"))
      (node (ref "IC4") (pin "1") (pinfunction "DVDT_1") (pintype "input"))
    )
    (net (code "49") (name "Net-(IC4-ILIM)") (class "Default")
      (node (ref "IC4") (pin "7") (pinfunction "ILIM_7") (pintype "input"))
      (node (ref "R14") (pin "1") (pinfunction "1_1") (pintype "passive"))
    )
    (net (code "50") (name "Net-(IC4-~{FLT})") (class "Default")
      (node (ref "IC4") (pin "6") (pinfunction "~{FLT}_6") (pintype "open_collector"))
      (node (ref "POWERFAIL") (pin "C") (pinfunction "C_C") (pintype "passive"))
    )
    (net (code "51") (name "Net-(JP8-1)") (class "Default")
      (node (ref "JP8") (pin "P1") (pinfunction "1_P1") (pintype "passive"))
      (node (ref "U2") (pin "2") (pinfunction "A_OUT1_2") (pintype "output"))
    )
    (net (code "52") (name "Net-(JP8-2)") (class "Default")
      (node (ref "JP8") (pin "P2") (pinfunction "2_P2") (pintype "passive"))
      (node (ref "U2") (pin "4") (pinfunction "A_OUT2_4") (pintype "output"))
    )
    (net (code "53") (name "Net-(JP8-4)") (class "Default")
      (node (ref "JP8") (pin "P4") (pinfunction "4_P4") (pintype "passive"))
      (node (ref "U2") (pin "5") (pinfunction "B_OUT2_5") (pintype "output"))
    )
    (net (code "54") (name "Net-(JP8-5)") (class "Default")
      (node (ref "JP8") (pin "P5") (pinfunction "5_P5") (pintype "passive"))
      (node (ref "U2") (pin "7") (pinfunction "B_OUT1_7") (pintype "output"))
    )
    (net (code "55") (name "Net-(L-PadA)") (class "Default")
      (node (ref "L") (pin "A") (pinfunction "A_A") (pintype "passive"))
      (node (ref "R7") (pin "1") (pinfunction "1_1") (pintype "passive"))
    )
    (net (code "56") (name "Net-(ON/OFF-PadO1)") (class "Default")
      (node (ref "ON/OFF") (pin "O1") (pinfunction "O1_O1") (pintype "passive"))
      (node (ref "R1") (pin "2") (pinfunction "2_2") (pintype "passive"))
    )
    (net (code "57") (name "Net-(POWERFAIL-PadA)") (class "Default")
      (node (ref "POWERFAIL") (pin "A") (pinfunction "A_A") (pintype "passive"))
      (node (ref "R15") (pin "2") (pinfunction "2_2") (pintype "passive"))
    )
    (net (code "58") (name "Net-(POWEROK-PadA)") (class "Default")
      (node (ref "POWEROK") (pin "A") (pinfunction "A_A") (pintype "passive"))
      (node (ref "R2") (pin "2") (pinfunction "2_2") (pintype "passive"))
    )
    (net (code "59") (name "Net-(Q2-D)") (class "Default")
      (node (ref "Q2") (pin "5678") (pinfunction "D_5678") (pintype "passive"))
      (node (ref "X2") (pin "PWR") (pinfunction "PWR_PWR") (pintype "power_in"))
    )
    (net (code "60") (name "Net-(U1-IN)") (class "Default")
      (node (ref "C2") (pin "2") (pinfunction "2_2") (pintype "passive"))
      (node (ref "D2") (pin "C") (pinfunction "C_C") (pintype "passive"))
      (node (ref "D3") (pin "C") (pinfunction "C_C") (pintype "passive"))
      (node (ref "R8") (pin "1") (pinfunction "1_1") (pintype "passive"))
      (node (ref "U1") (pin "1") (pinfunction "IN_1") (pintype "power_in"))
    )
    (net (code "61") (name "Net-(U2-VCP)") (class "Default")
      (node (ref "C6") (pin "2") (pinfunction "2_2") (pintype "passive"))
      (node (ref "U2") (pin "11") (pinfunction "VCP_11") (pintype "bidirectional"))
    )
    (net (code "62") (name "Net-(U5-IN_N)") (class "Default")
      (node (ref "R12") (pin "2") (pinfunction "2_2") (pintype "passive"))
      (node (ref "U5") (pin "4") (pinfunction "IN_N_4") (pintype "input"))
    )
    (net (code "63") (name "Net-(U5-IN_P)") (class "Default")
      (node (ref "R13") (pin "2") (pinfunction "2_2") (pintype "passive"))
      (node (ref "U5") (pin "3") (pinfunction "IN_P_3") (pintype "input"))
    )
    (net (code "64") (name "Net-(VR2-S)") (class "Default")
      (node (ref "C13") (pin "2") (pinfunction "2_2") (pintype "passive"))
      (node (ref "VR2") (pin "2") (pinfunction "S_2") (pintype "passive"))
    )
    (net (code "65") (name "SEESAW_RESET") (class "Default")
      (node (ref "IC1") (pin "40") (pinfunction "/RESET_40") (pintype "bidirectional"))
      (node (ref "SJ1") (pin "1") (pinfunction "1_1") (pintype "passive"))
      (node (ref "TP3") (pin "TP") (pinfunction "TP_TP") (pintype "input"))
    )
    (net (code "66") (name "SERVO1") (class "Default")
      (node (ref "IC1") (pin "26") (pinfunction "PA17/I2C/I1/SERCOM1+3.1_26") (pintype "bidirectional"))
      (node (ref "SERVO") (pin "1") (pinfunction "1_1") (pintype "passive"))
    )
    (net (code "67") (name "SERVO2") (class "Default")
      (node (ref "IC1") (pin "25") (pinfunction "PA16/I2C/I0/SERCOM1+3.0_25") (pintype "bidirectional"))
      (node (ref "SERVO") (pin "4") (pinfunction "4_4") (pintype "passive"))
    )
    (net (code "68") (name "SERVO3") (class "Default")
      (node (ref "IC1") (pin "24") (pinfunction "PA15/I15/SERCOM2+4.3_24") (pintype "bidirectional"))
      (node (ref "SERVO") (pin "7") (pinfunction "7_7") (pintype "passive"))
    )
    (net (code "69") (name "SERVO4") (class "Default")
      (node (ref "IC1") (pin "23") (pinfunction "PA14/I14/SERCOM2+4.2_23") (pintype "bidirectional"))
      (node (ref "SERVO") (pin "10") (pinfunction "10_10") (pintype "passive"))
    )
    (net (code "70") (name "SPKR+") (class "Default")
      (node (ref "SPKR") (pin "2") (pinfunction "2_2") (pintype "passive"))
      (node (ref "U5") (pin "5") (pinfunction "VO_P_5") (pintype "output"))
    )
    (net (code "71") (name "SPKR-") (class "Default")
      (node (ref "SPKR") (pin "1") (pinfunction "1_1") (pintype "passive"))
      (node (ref "U5") (pin "8") (pinfunction "VO_N_8") (pintype "output"))
    )
    (net (code "72") (name "SWCLK") (class "Default")
      (node (ref "IC1") (pin "45") (pinfunction "PA30/I10/SECOM1.2/SWCLK_45") (pintype "bidirectional"))
      (node (ref "R18") (pin "1") (pinfunction "1_1") (pintype "passive"))
      (node (ref "TP2") (pin "TP") (pinfunction "TP_TP") (pintype "input"))
    )
    (net (code "73") (name "SWDIO") (class "Default")
      (node (ref "IC1") (pin "46") (pinfunction "PA31/I11/SECOM1.3/SWDIO_46") (pintype "bidirectional"))
      (node (ref "TP1") (pin "TP") (pinfunction "TP_TP") (pintype "input"))
    )
    (net (code "74") (name "VBUS") (class "Default")
      (node (ref "CN1") (pin "VBUS") (pinfunction "VBUS_VBUS") (pintype "power_in"))
      (node (ref "D3") (pin "A") (pinfunction "A_A") (pintype "passive"))
    )
    (net (code "75") (name "VDD") (class "Default")
      (node (ref "C11") (pin "1") (pinfunction "1_1") (pintype "passive"))
      (node (ref "C12") (pin "1") (pinfunction "1_1") (pintype "passive"))
      (node (ref "C19") (pin "1") (pinfunction "1_1") (pintype "passive"))
      (node (ref "FB1") (pin "2") (pinfunction "P$2_2") (pintype "passive"))
      (node (ref "IC1") (pin "17") (pinfunction "VDDIO_17") (pintype "power_in"))
      (node (ref "IC1") (pin "36") (pinfunction "VDDIO_36") (pintype "power_in"))
      (node (ref "IC1") (pin "44") (pinfunction "VDDIN_44") (pintype "power_in"))
      (node (ref "IC1") (pin "6") (pinfunction "VDDA_6") (pintype "power_in"))
      (node (ref "LED1") (pin "2") (pinfunction "VDD_2") (pintype "power_in"))
      (node (ref "R17") (pin "2") (pinfunction "2_2") (pintype "passive"))
      (node (ref "R18") (pin "2") (pinfunction "2_2") (pintype "passive"))
    )
    (net (code "76") (name "VIN") (class "Default")
      (node (ref "C21") (pin "1") (pinfunction "1_1") (pintype "passive"))
      (node (ref "C22") (pin "1") (pinfunction "1_1") (pintype "passive"))
      (node (ref "D2") (pin "A") (pinfunction "A_A") (pintype "passive"))
      (node (ref "IC4") (pin "3") (pinfunction "IN_3") (pintype "power_in"))
      (node (ref "IC4") (pin "4") (pinfunction "IN_4") (pintype "power_in"))
      (node (ref "Q2") (pin "1") (pinfunction "S_1") (pintype "passive"))
      (node (ref "Q2") (pin "2") (pinfunction "S_2") (pintype "passive"))
      (node (ref "Q2") (pin "3") (pinfunction "S_3") (pintype "passive"))
      (node (ref "R1") (pin "1") (pinfunction "1_1") (pintype "passive"))
      (node (ref "R10") (pin "1") (pinfunction "1_1") (pintype "passive"))
      (node (ref "R9") (pin "1") (pinfunction "1_1") (pintype "passive"))
    )
    (net (code "77") (name "VINT") (class "Default")
      (node (ref "C5") (pin "1") (pinfunction "1_1") (pintype "passive"))
      (node (ref "U2") (pin "14") (pinfunction "VINT_14") (pintype "power_in"))
    )
    (net (code "78") (name "VIN_SENSE") (class "Default")
      (node (ref "IC1") (pin "48") (pinfunction "PB03/I3/AIN11/SERCOM5.1_48") (pintype "bidirectional"))
      (node (ref "R16") (pin "1") (pinfunction "1_1") (pintype "passive"))
      (node (ref "R9") (pin "2") (pinfunction "2_2") (pintype "passive"))
    )
    (net (code "79") (name "unconnected-(CN1-PadID)") (class "Default")
      (node (ref "CN1") (pin "ID") (pinfunction "ID_ID") (pintype "bidirectional"))
    )
    (net (code "80") (name "unconnected-(IC1-PA21{slash}I5{slash}SERCOM3+5.3{slash}I2SFS0-Pad30)") (class "Default")
      (node (ref "IC1") (pin "30") (pinfunction "PA21/I5/SERCOM3+5.3/I2SFS0_30") (pintype "bidirectional"))
    )
    (net (code "81") (name "unconnected-(IC1-PB02{slash}I2{slash}AIN10{slash}SERCOM5.0-Pad47)") (class "Default")
      (node (ref "IC1") (pin "47") (pinfunction "PB02/I2/AIN10/SERCOM5.0_47") (pintype "bidirectional"))
    )
    (net (code "82") (name "unconnected-(IC1-PB23{slash}I7{slash}SERCOM5.3-Pad38)") (class "Default")
      (node (ref "IC1") (pin "38") (pinfunction "PB23/I7/SERCOM5.3_38") (pintype "bidirectional"))
    )
    (net (code "83") (name "unconnected-(IC2-O3-Pad14)") (class "Default")
      (node (ref "IC2") (pin "14") (pinfunction "O3_14") (pintype "open_collector"))
    )
    (net (code "84") (name "unconnected-(IC2-O4-Pad13)") (class "Default")
      (node (ref "IC2") (pin "13") (pinfunction "O4_13") (pintype "open_collector"))
    )
    (net (code "85") (name "unconnected-(IC2-O5-Pad12)") (class "Default")
      (node (ref "IC2") (pin "12") (pinfunction "O5_12") (pintype "open_collector"))
    )
    (net (code "86") (name "unconnected-(LED1-DO-Pad3)") (class "Default")
      (node (ref "LED1") (pin "3") (pinfunction "DO_3") (pintype "output"))
    )
    (net (code "87") (name "unconnected-(ON/OFF-PadS1)") (class "Default")
      (node (ref "ON/OFF") (pin "S1") (pinfunction "S1_S1") (pintype "passive"))
    )
    (net (code "88") (name "unconnected-(ON/OFF-PadS2)") (class "Default")
      (node (ref "ON/OFF") (pin "S2") (pinfunction "S2_S2") (pintype "passive"))
    )
    (net (code "89") (name "unconnected-(U1-P4-Pad4)") (class "Default")
      (node (ref "U1") (pin "4") (pinfunction "P4_4") (pintype "bidirectional"))
    )
    (net (code "90") (name "unconnected-(U5-NC-Pad2)") (class "Default")
      (node (ref "U5") (pin "2") (pinfunction "NC_2") (pintype "no_connect"))
    )
    (net (code "91") (name "~{RESET}") (class "Default")
      (node (ref "C20") (pin "1") (pinfunction "1_1") (pintype "passive"))
      (node (ref "R17") (pin "1") (pinfunction "1_1") (pintype "passive"))
      (node (ref "SJ1") (pin "2") (pinfunction "2_2") (pintype "passive"))
      (node (ref "SW1") (pin "B") (pinfunction "S_B") (pintype "passive"))
      (node (ref "SW1") (pin "B'") (pinfunction "S1_B'") (pintype "passive"))
    )
    (net (code "92") (name "~{TPSEN}") (class "Default")
      (node (ref "IC4") (pin "2") (pinfunction "~{EN/OVLO}_2") (pintype "input"))
      (node (ref "ON/OFF") (pin "P1") (pinfunction "P1_P1") (pintype "passive"))
      (node (ref "R10") (pin "2") (pinfunction "2_2") (pintype "passive"))
      (node (ref "R11") (pin "1") (pinfunction "1_1") (pintype "passive"))
    )
  )
)
